# receiver.net
KiCad netlist of a schematic drawn in EAGLE
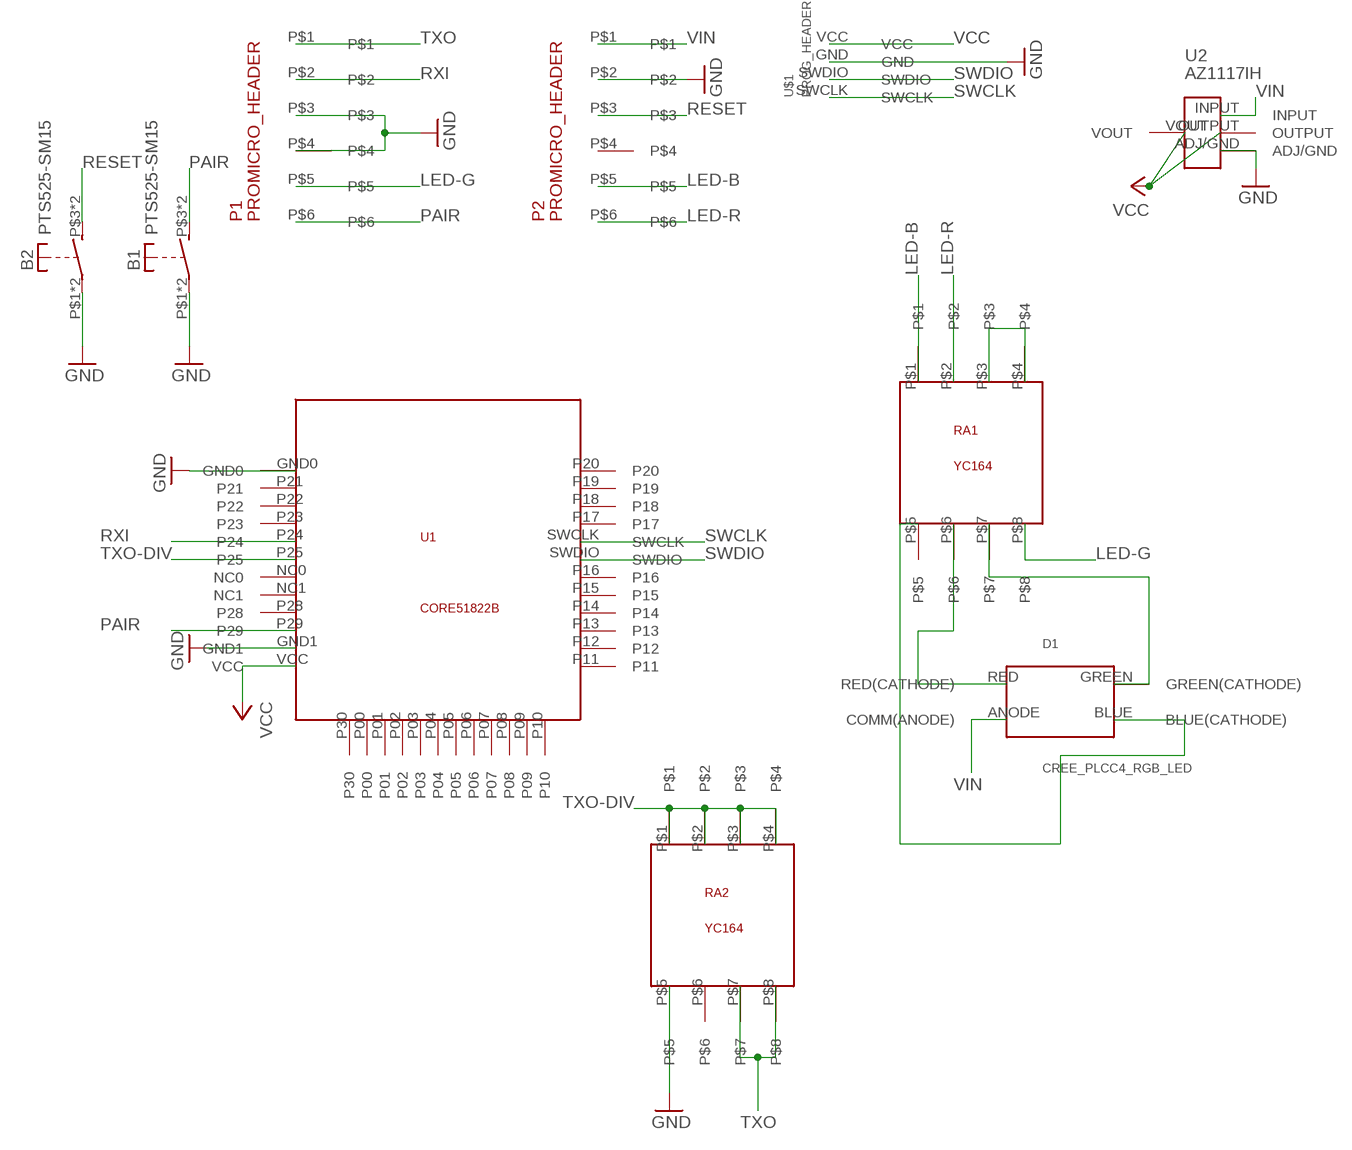
[diagram p0: schematic, sheet 1]

(export (version "E")
  (design (tool "Eeschema 10.0.6"))
  (components
    (comp (ref "B1")
      (value "PTS525-SM15")
      (footprint "eagle-import:PTS525-SM15")
      (libsource (lib "eagle-import") (part "PTS525-SM15"))
    )
    (comp (ref "B2")
      (value "PTS525-SM15")
      (footprint "eagle-import:PTS525-SM15")
      (libsource (lib "eagle-import") (part "PTS525-SM15"))
    )
    (comp (ref "D1")
      (value "CREE_PLCC4_RGB_LED")
      (footprint "eagle-import:4-PLCC")
      (libsource (lib "eagle-import") (part "CREE_PLCC4_RGB_LED"))
    )
    (comp (ref "P1")
      (value "PROMICRO_HEADER")
      (footprint "eagle-import:PROMICRO_HEADER")
      (libsource (lib "eagle-import") (part "PROMICRO_HEADER"))
    )
    (comp (ref "P2")
      (value "PROMICRO_HEADER")
      (footprint "eagle-import:PROMICRO_HEADER")
      (libsource (lib "eagle-import") (part "PROMICRO_HEADER"))
    )
    (comp (ref "RA1")
      (value "YC164")
      (footprint "eagle-import:YC164")
      (libsource (lib "eagle-import") (part "YC164"))
    )
    (comp (ref "RA2")
      (value "YC164")
      (footprint "eagle-import:YC164")
      (libsource (lib "eagle-import") (part "YC164"))
    )
    (comp (ref "U$1")
      (value "PROG_HEADER")
      (footprint "eagle-import:PROG_HEADER")
      (libsource (lib "eagle-import") (part "PROG_HEADER"))
    )
    (comp (ref "U1")
      (value "CORE51822B")
      (footprint "eagle-import:CORE51822B")
      (libsource (lib "eagle-import") (part "CORE51822B"))
    )
    (comp (ref "U2")
      (value "AZ1117IH")
      (footprint "eagle-import:AZ1117IH")
      (libsource (lib "eagle-import") (part "AZ1117IH"))
    )
  )
  (nets
    (net (code "1") (name "/LED-B") (class "Default")
      (node (ref "P2") (pin "P$5") (pinfunction "P$5_P$5") (pintype "bidirectional"))
      (node (ref "RA1") (pin "P$1") (pinfunction "P$1_P$1") (pintype "bidirectional"))
    )
    (net (code "2") (name "/LED-G") (class "Default")
      (node (ref "P1") (pin "P$5") (pinfunction "P$5_P$5") (pintype "bidirectional"))
      (node (ref "RA1") (pin "P$8") (pinfunction "P$8_P$8") (pintype "bidirectional"))
    )
    (net (code "3") (name "/LED-R") (class "Default")
      (node (ref "P2") (pin "P$6") (pinfunction "P$6_P$6") (pintype "bidirectional"))
      (node (ref "RA1") (pin "P$2") (pinfunction "P$2_P$2") (pintype "bidirectional"))
    )
    (net (code "4") (name "/PAIR") (class "Default")
      (node (ref "B1") (pin "P$3") (pinfunction "S_P$3") (pintype "passive"))
      (node (ref "B1") (pin "P$4") (pinfunction "S_P$4") (pintype "passive"))
      (node (ref "P1") (pin "P$6") (pinfunction "P$6_P$6") (pintype "bidirectional"))
      (node (ref "U1") (pin "P29") (pinfunction "P29_P29") (pintype "bidirectional"))
    )
    (net (code "5") (name "/RESET") (class "Default")
      (node (ref "B2") (pin "P$3") (pinfunction "S_P$3") (pintype "passive"))
      (node (ref "B2") (pin "P$4") (pinfunction "S_P$4") (pintype "passive"))
      (node (ref "P2") (pin "P$3") (pinfunction "P$3_P$3") (pintype "bidirectional"))
    )
    (net (code "6") (name "/RXI") (class "Default")
      (node (ref "P1") (pin "P$2") (pinfunction "P$2_P$2") (pintype "bidirectional"))
      (node (ref "U1") (pin "P24") (pinfunction "P24_P24") (pintype "bidirectional"))
    )
    (net (code "7") (name "/SWCLK") (class "Default")
      (node (ref "U$1") (pin "SWCLK") (pinfunction "SWCLK_SWCLK") (pintype "bidirectional"))
      (node (ref "U1") (pin "SWCLK") (pinfunction "SWCLK_SWCLK") (pintype "bidirectional"))
    )
    (net (code "8") (name "/SWDIO") (class "Default")
      (node (ref "U$1") (pin "SWDIO") (pinfunction "SWDIO_SWDIO") (pintype "bidirectional"))
      (node (ref "U1") (pin "SWDIO") (pinfunction "SWDIO_SWDIO") (pintype "bidirectional"))
    )
    (net (code "9") (name "/TXO") (class "Default")
      (node (ref "P1") (pin "P$1") (pinfunction "P$1_P$1") (pintype "bidirectional"))
      (node (ref "RA2") (pin "P$7") (pinfunction "P$7_P$7") (pintype "bidirectional"))
      (node (ref "RA2") (pin "P$8") (pinfunction "P$8_P$8") (pintype "bidirectional"))
    )
    (net (code "10") (name "/TXO-DIV") (class "Default")
      (node (ref "RA2") (pin "P$1") (pinfunction "P$1_P$1") (pintype "bidirectional"))
      (node (ref "RA2") (pin "P$2") (pinfunction "P$2_P$2") (pintype "bidirectional"))
      (node (ref "RA2") (pin "P$3") (pinfunction "P$3_P$3") (pintype "bidirectional"))
      (node (ref "RA2") (pin "P$4") (pinfunction "P$4_P$4") (pintype "bidirectional"))
      (node (ref "U1") (pin "P25") (pinfunction "P25_P25") (pintype "bidirectional"))
    )
    (net (code "11") (name "/VIN") (class "Default")
      (node (ref "D1") (pin "ANODE") (pinfunction "COMM(ANODE)_ANODE") (pintype "bidirectional"))
      (node (ref "P2") (pin "P$1") (pinfunction "P$1_P$1") (pintype "bidirectional"))
      (node (ref "U2") (pin "INPUT") (pinfunction "INPUT_INPUT") (pintype "bidirectional"))
    )
    (net (code "12") (name "GND") (class "Default")
      (node (ref "B1") (pin "P$1") (pinfunction "P_P$1") (pintype "passive"))
      (node (ref "B1") (pin "P$2") (pinfunction "P_P$2") (pintype "passive"))
      (node (ref "B2") (pin "P$1") (pinfunction "P_P$1") (pintype "passive"))
      (node (ref "B2") (pin "P$2") (pinfunction "P_P$2") (pintype "passive"))
      (node (ref "P1") (pin "P$3") (pinfunction "P$3_P$3") (pintype "bidirectional"))
      (node (ref "P1") (pin "P$4") (pinfunction "P$4_P$4") (pintype "bidirectional"))
      (node (ref "P2") (pin "P$2") (pinfunction "P$2_P$2") (pintype "bidirectional"))
      (node (ref "RA2") (pin "P$5") (pinfunction "P$5_P$5") (pintype "bidirectional"))
      (node (ref "U$1") (pin "GND") (pinfunction "GND_GND") (pintype "bidirectional"))
      (node (ref "U1") (pin "GND0") (pinfunction "GND0_GND0") (pintype "bidirectional"))
      (node (ref "U1") (pin "GND1") (pinfunction "GND1_GND1") (pintype "bidirectional"))
      (node (ref "U2") (pin "ADJ/GND") (pinfunction "ADJ/GND_ADJ/GND") (pintype "bidirectional"))
    )
    (net (code "13") (name "Net-(D1-BLUE(CATHODE))") (class "Default")
      (node (ref "D1") (pin "BLUE") (pinfunction "BLUE(CATHODE)_BLUE") (pintype "bidirectional"))
      (node (ref "RA1") (pin "P$5") (pinfunction "P$5_P$5") (pintype "bidirectional"))
    )
    (net (code "14") (name "Net-(D1-GREEN(CATHODE))") (class "Default")
      (node (ref "D1") (pin "GREEN") (pinfunction "GREEN(CATHODE)_GREEN") (pintype "bidirectional"))
      (node (ref "RA1") (pin "P$7") (pinfunction "P$7_P$7") (pintype "bidirectional"))
    )
    (net (code "15") (name "Net-(D1-RED(CATHODE))") (class "Default")
      (node (ref "D1") (pin "RED") (pinfunction "RED(CATHODE)_RED") (pintype "bidirectional"))
      (node (ref "RA1") (pin "P$6") (pinfunction "P$6_P$6") (pintype "bidirectional"))
    )
    (net (code "16") (name "Net-(RA1-PadP$3)") (class "Default")
      (node (ref "RA1") (pin "P$3") (pinfunction "P$3_P$3") (pintype "bidirectional"))
      (node (ref "RA1") (pin "P$4") (pinfunction "P$4_P$4") (pintype "bidirectional"))
    )
    (net (code "17") (name "VCC") (class "Default")
      (node (ref "U$1") (pin "VCC") (pinfunction "VCC_VCC") (pintype "bidirectional"))
      (node (ref "U1") (pin "VCC") (pinfunction "VCC_VCC") (pintype "bidirectional"))
      (node (ref "U2") (pin "OUTPUT") (pinfunction "OUTPUT_OUTPUT") (pintype "bidirectional"))
      (node (ref "U2") (pin "VOUT") (pinfunction "VOUT_VOUT") (pintype "bidirectional"))
    )
    (net (code "18") (name "unconnected-(P2-PadP$4)") (class "Default")
      (node (ref "P2") (pin "P$4") (pinfunction "P$4_P$4") (pintype "bidirectional"))
    )
    (net (code "19") (name "unconnected-(RA2-PadP$6)") (class "Default")
      (node (ref "RA2") (pin "P$6") (pinfunction "P$6_P$6") (pintype "bidirectional"))
    )
    (net (code "20") (name "unconnected-(U1-PadNC0)") (class "Default")
      (node (ref "U1") (pin "NC0") (pinfunction "NC0_NC0") (pintype "bidirectional"))
    )
    (net (code "21") (name "unconnected-(U1-PadNC1)") (class "Default")
      (node (ref "U1") (pin "NC1") (pinfunction "NC1_NC1") (pintype "bidirectional"))
    )
    (net (code "22") (name "unconnected-(U1-PadP00)") (class "Default")
      (node (ref "U1") (pin "P00") (pinfunction "P00_P00") (pintype "bidirectional"))
    )
    (net (code "23") (name "unconnected-(U1-PadP01)") (class "Default")
      (node (ref "U1") (pin "P01") (pinfunction "P01_P01") (pintype "bidirectional"))
    )
    (net (code "24") (name "unconnected-(U1-PadP02)") (class "Default")
      (node (ref "U1") (pin "P02") (pinfunction "P02_P02") (pintype "bidirectional"))
    )
    (net (code "25") (name "unconnected-(U1-PadP03)") (class "Default")
      (node (ref "U1") (pin "P03") (pinfunction "P03_P03") (pintype "bidirectional"))
    )
    (net (code "26") (name "unconnected-(U1-PadP04)") (class "Default")
      (node (ref "U1") (pin "P04") (pinfunction "P04_P04") (pintype "bidirectional"))
    )
    (net (code "27") (name "unconnected-(U1-PadP05)") (class "Default")
      (node (ref "U1") (pin "P05") (pinfunction "P05_P05") (pintype "bidirectional"))
    )
    (net (code "28") (name "unconnected-(U1-PadP06)") (class "Default")
      (node (ref "U1") (pin "P06") (pinfunction "P06_P06") (pintype "bidirectional"))
    )
    (net (code "29") (name "unconnected-(U1-PadP07)") (class "Default")
      (node (ref "U1") (pin "P07") (pinfunction "P07_P07") (pintype "bidirectional"))
    )
    (net (code "30") (name "unconnected-(U1-PadP08)") (class "Default")
      (node (ref "U1") (pin "P08") (pinfunction "P08_P08") (pintype "bidirectional"))
    )
    (net (code "31") (name "unconnected-(U1-PadP09)") (class "Default")
      (node (ref "U1") (pin "P09") (pinfunction "P09_P09") (pintype "bidirectional"))
    )
    (net (code "32") (name "unconnected-(U1-PadP10)") (class "Default")
      (node (ref "U1") (pin "P10") (pinfunction "P10_P10") (pintype "bidirectional"))
    )
    (net (code "33") (name "unconnected-(U1-PadP11)") (class "Default")
      (node (ref "U1") (pin "P11") (pinfunction "P11_P11") (pintype "bidirectional"))
    )
    (net (code "34") (name "unconnected-(U1-PadP12)") (class "Default")
      (node (ref "U1") (pin "P12") (pinfunction "P12_P12") (pintype "bidirectional"))
    )
    (net (code "35") (name "unconnected-(U1-PadP13)") (class "Default")
      (node (ref "U1") (pin "P13") (pinfunction "P13_P13") (pintype "bidirectional"))
    )
    (net (code "36") (name "unconnected-(U1-PadP14)") (class "Default")
      (node (ref "U1") (pin "P14") (pinfunction "P14_P14") (pintype "bidirectional"))
    )
    (net (code "37") (name "unconnected-(U1-PadP15)") (class "Default")
      (node (ref "U1") (pin "P15") (pinfunction "P15_P15") (pintype "bidirectional"))
    )
    (net (code "38") (name "unconnected-(U1-PadP16)") (class "Default")
      (node (ref "U1") (pin "P16") (pinfunction "P16_P16") (pintype "bidirectional"))
    )
    (net (code "39") (name "unconnected-(U1-PadP17)") (class "Default")
      (node (ref "U1") (pin "P17") (pinfunction "P17_P17") (pintype "bidirectional"))
    )
    (net (code "40") (name "unconnected-(U1-PadP18)") (class "Default")
      (node (ref "U1") (pin "P18") (pinfunction "P18_P18") (pintype "bidirectional"))
    )
    (net (code "41") (name "unconnected-(U1-PadP19)") (class "Default")
      (node (ref "U1") (pin "P19") (pinfunction "P19_P19") (pintype "bidirectional"))
    )
    (net (code "42") (name "unconnected-(U1-PadP20)") (class "Default")
      (node (ref "U1") (pin "P20") (pinfunction "P20_P20") (pintype "bidirectional"))
    )
    (net (code "43") (name "unconnected-(U1-PadP21)") (class "Default")
      (node (ref "U1") (pin "P21") (pinfunction "P21_P21") (pintype "bidirectional"))
    )
    (net (code "44") (name "unconnected-(U1-PadP22)") (class "Default")
      (node (ref "U1") (pin "P22") (pinfunction "P22_P22") (pintype "bidirectional"))
    )
    (net (code "45") (name "unconnected-(U1-PadP23)") (class "Default")
      (node (ref "U1") (pin "P23") (pinfunction "P23_P23") (pintype "bidirectional"))
    )
    (net (code "46") (name "unconnected-(U1-PadP28)") (class "Default")
      (node (ref "U1") (pin "P28") (pinfunction "P28_P28") (pintype "bidirectional"))
    )
    (net (code "47") (name "unconnected-(U1-PadP30)") (class "Default")
      (node (ref "U1") (pin "P30") (pinfunction "P30_P30") (pintype "bidirectional"))
    )
  )
)
